# InputDigital.net
KiCad netlist of a schematic drawn in Altium Designer
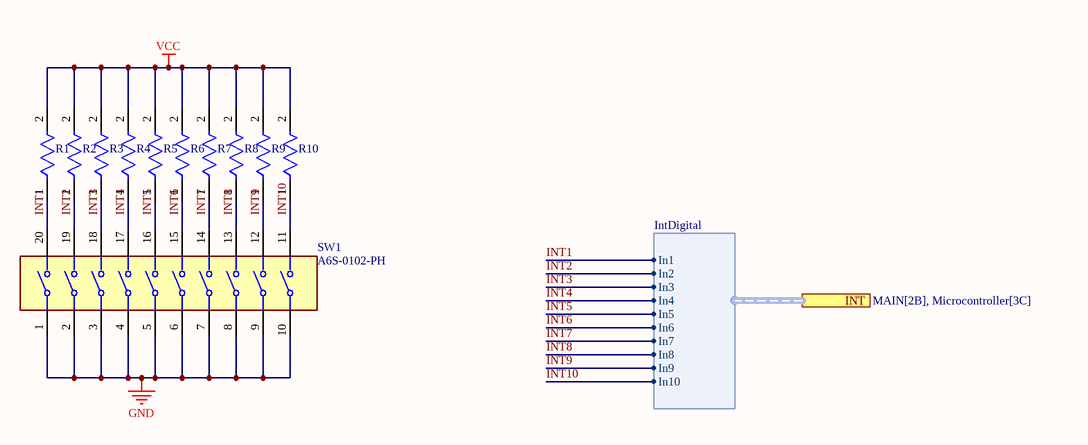
[diagram p0: InputDigital.SchDoc]

(export (version "E")
  (design (tool "Eeschema 10.0.6"))
  (components
    (comp (ref "R1")
      (value "RT0805BRD07249RL")
      (footprint "FP-RT0805-MFG")
      (description "RES SMD 249 OHM 0.1% 1/8W 0805")
      (fields
        (field (name "OCTOPART") "https://octopart.com/rt0805brd07249rl-yageo-1410573")
        (field (name "MANUFACTURER") "Yageo")
      )
      (libsource (lib "Ejemplo2") (part "CMP-03412-035801-1"))
    )
    (comp (ref "R2")
      (value "RT0805BRD07249RL")
      (footprint "FP-RT0805-MFG")
      (description "RES SMD 249 OHM 0.1% 1/8W 0805")
      (fields
        (field (name "OCTOPART") "https://octopart.com/rt0805brd07249rl-yageo-1410573")
        (field (name "MANUFACTURER") "Yageo")
      )
      (libsource (lib "Ejemplo2") (part "CMP-03412-035801-1"))
    )
    (comp (ref "R3")
      (value "RT0805BRD07249RL")
      (footprint "FP-RT0805-MFG")
      (description "RES SMD 249 OHM 0.1% 1/8W 0805")
      (fields
        (field (name "OCTOPART") "https://octopart.com/rt0805brd07249rl-yageo-1410573")
        (field (name "MANUFACTURER") "Yageo")
      )
      (libsource (lib "Ejemplo2") (part "CMP-03412-035801-1"))
    )
    (comp (ref "R4")
      (value "RT0805BRD07249RL")
      (footprint "FP-RT0805-MFG")
      (description "RES SMD 249 OHM 0.1% 1/8W 0805")
      (fields
        (field (name "OCTOPART") "https://octopart.com/rt0805brd07249rl-yageo-1410573")
        (field (name "MANUFACTURER") "Yageo")
      )
      (libsource (lib "Ejemplo2") (part "CMP-03412-035801-1"))
    )
    (comp (ref "R5")
      (value "RT0805BRD07249RL")
      (footprint "FP-RT0805-MFG")
      (description "RES SMD 249 OHM 0.1% 1/8W 0805")
      (fields
        (field (name "OCTOPART") "https://octopart.com/rt0805brd07249rl-yageo-1410573")
        (field (name "MANUFACTURER") "Yageo")
      )
      (libsource (lib "Ejemplo2") (part "CMP-03412-035801-1"))
    )
    (comp (ref "R6")
      (value "RT0805BRD07249RL")
      (footprint "FP-RT0805-MFG")
      (description "RES SMD 249 OHM 0.1% 1/8W 0805")
      (fields
        (field (name "OCTOPART") "https://octopart.com/rt0805brd07249rl-yageo-1410573")
        (field (name "MANUFACTURER") "Yageo")
      )
      (libsource (lib "Ejemplo2") (part "CMP-03412-035801-1"))
    )
    (comp (ref "R7")
      (value "RT0805BRD07249RL")
      (footprint "FP-RT0805-MFG")
      (description "RES SMD 249 OHM 0.1% 1/8W 0805")
      (fields
        (field (name "OCTOPART") "https://octopart.com/rt0805brd07249rl-yageo-1410573")
        (field (name "MANUFACTURER") "Yageo")
      )
      (libsource (lib "Ejemplo2") (part "CMP-03412-035801-1"))
    )
    (comp (ref "R8")
      (value "RT0805BRD07249RL")
      (footprint "FP-RT0805-MFG")
      (description "RES SMD 249 OHM 0.1% 1/8W 0805")
      (fields
        (field (name "OCTOPART") "https://octopart.com/rt0805brd07249rl-yageo-1410573")
        (field (name "MANUFACTURER") "Yageo")
      )
      (libsource (lib "Ejemplo2") (part "CMP-03412-035801-1"))
    )
    (comp (ref "R9")
      (value "RT0805BRD07249RL")
      (footprint "FP-RT0805-MFG")
      (description "RES SMD 249 OHM 0.1% 1/8W 0805")
      (fields
        (field (name "OCTOPART") "https://octopart.com/rt0805brd07249rl-yageo-1410573")
        (field (name "MANUFACTURER") "Yageo")
      )
      (libsource (lib "Ejemplo2") (part "CMP-03412-035801-1"))
    )
    (comp (ref "R10")
      (value "RT0805BRD07249RL")
      (footprint "FP-RT0805-MFG")
      (description "RES SMD 249 OHM 0.1% 1/8W 0805")
      (fields
        (field (name "OCTOPART") "https://octopart.com/rt0805brd07249rl-yageo-1410573")
        (field (name "MANUFACTURER") "Yageo")
      )
      (libsource (lib "Ejemplo2") (part "CMP-03412-035801-1"))
    )
    (comp (ref "SW1")
      (value "A6S-0102-PH")
      (footprint "FP-A6S-0102-PH-MFG")
      (description "SWITCH SLIDE DIP SPST 25MA 24V")
      (libsource (lib "Ejemplo2") (part "CMP-08827-000074-1"))
    )
  )
  (nets
    (net (code "2") (name "/INT1") (class "Default")
      (node (ref "R1") (pin "1") (pinfunction "1_1") (pintype "passive"))
      (node (ref "SW1") (pin "20") (pinfunction "20_20") (pintype "passive"))
    )
    (net (code "3") (name "/INT2") (class "Default")
      (node (ref "R2") (pin "1") (pinfunction "1_1") (pintype "passive"))
      (node (ref "SW1") (pin "19") (pinfunction "19_19") (pintype "passive"))
    )
    (net (code "4") (name "/INT3") (class "Default")
      (node (ref "R3") (pin "1") (pinfunction "1_1") (pintype "passive"))
      (node (ref "SW1") (pin "18") (pinfunction "18_18") (pintype "passive"))
    )
    (net (code "5") (name "/INT4") (class "Default")
      (node (ref "R4") (pin "1") (pinfunction "1_1") (pintype "passive"))
      (node (ref "SW1") (pin "17") (pinfunction "17_17") (pintype "passive"))
    )
    (net (code "6") (name "/INT5") (class "Default")
      (node (ref "R5") (pin "1") (pinfunction "1_1") (pintype "passive"))
      (node (ref "SW1") (pin "16") (pinfunction "16_16") (pintype "passive"))
    )
    (net (code "7") (name "/INT6") (class "Default")
      (node (ref "R6") (pin "1") (pinfunction "1_1") (pintype "passive"))
      (node (ref "SW1") (pin "15") (pinfunction "15_15") (pintype "passive"))
    )
    (net (code "8") (name "/INT7") (class "Default")
      (node (ref "R7") (pin "1") (pinfunction "1_1") (pintype "passive"))
      (node (ref "SW1") (pin "14") (pinfunction "14_14") (pintype "passive"))
    )
    (net (code "9") (name "/INT8") (class "Default")
      (node (ref "R8") (pin "1") (pinfunction "1_1") (pintype "passive"))
      (node (ref "SW1") (pin "13") (pinfunction "13_13") (pintype "passive"))
    )
    (net (code "10") (name "/INT9") (class "Default")
      (node (ref "R9") (pin "1") (pinfunction "1_1") (pintype "passive"))
      (node (ref "SW1") (pin "12") (pinfunction "12_12") (pintype "passive"))
    )
    (net (code "11") (name "/INT10") (class "Default")
      (node (ref "R10") (pin "1") (pinfunction "1_1") (pintype "passive"))
      (node (ref "SW1") (pin "11") (pinfunction "11_11") (pintype "passive"))
    )
    (net (code "13") (name "GND") (class "Default")
      (node (ref "SW1") (pin "1") (pinfunction "1_1") (pintype "passive"))
      (node (ref "SW1") (pin "10") (pinfunction "10_10") (pintype "passive"))
      (node (ref "SW1") (pin "2") (pinfunction "2_2") (pintype "passive"))
      (node (ref "SW1") (pin "3") (pinfunction "3_3") (pintype "passive"))
      (node (ref "SW1") (pin "4") (pinfunction "4_4") (pintype "passive"))
      (node (ref "SW1") (pin "5") (pinfunction "5_5") (pintype "passive"))
      (node (ref "SW1") (pin "6") (pinfunction "6_6") (pintype "passive"))
      (node (ref "SW1") (pin "7") (pinfunction "7_7") (pintype "passive"))
      (node (ref "SW1") (pin "8") (pinfunction "8_8") (pintype "passive"))
      (node (ref "SW1") (pin "9") (pinfunction "9_9") (pintype "passive"))
    )
    (net (code "14") (name "VCC") (class "Default")
      (node (ref "R1") (pin "2") (pinfunction "2_2") (pintype "passive"))
      (node (ref "R10") (pin "2") (pinfunction "2_2") (pintype "passive"))
      (node (ref "R2") (pin "2") (pinfunction "2_2") (pintype "passive"))
      (node (ref "R3") (pin "2") (pinfunction "2_2") (pintype "passive"))
      (node (ref "R4") (pin "2") (pinfunction "2_2") (pintype "passive"))
      (node (ref "R5") (pin "2") (pinfunction "2_2") (pintype "passive"))
      (node (ref "R6") (pin "2") (pinfunction "2_2") (pintype "passive"))
      (node (ref "R7") (pin "2") (pinfunction "2_2") (pintype "passive"))
      (node (ref "R8") (pin "2") (pinfunction "2_2") (pintype "passive"))
      (node (ref "R9") (pin "2") (pinfunction "2_2") (pintype "passive"))
    )
  )
)
